# MCU1.net
KiCad netlist of a schematic drawn in Altium Designer
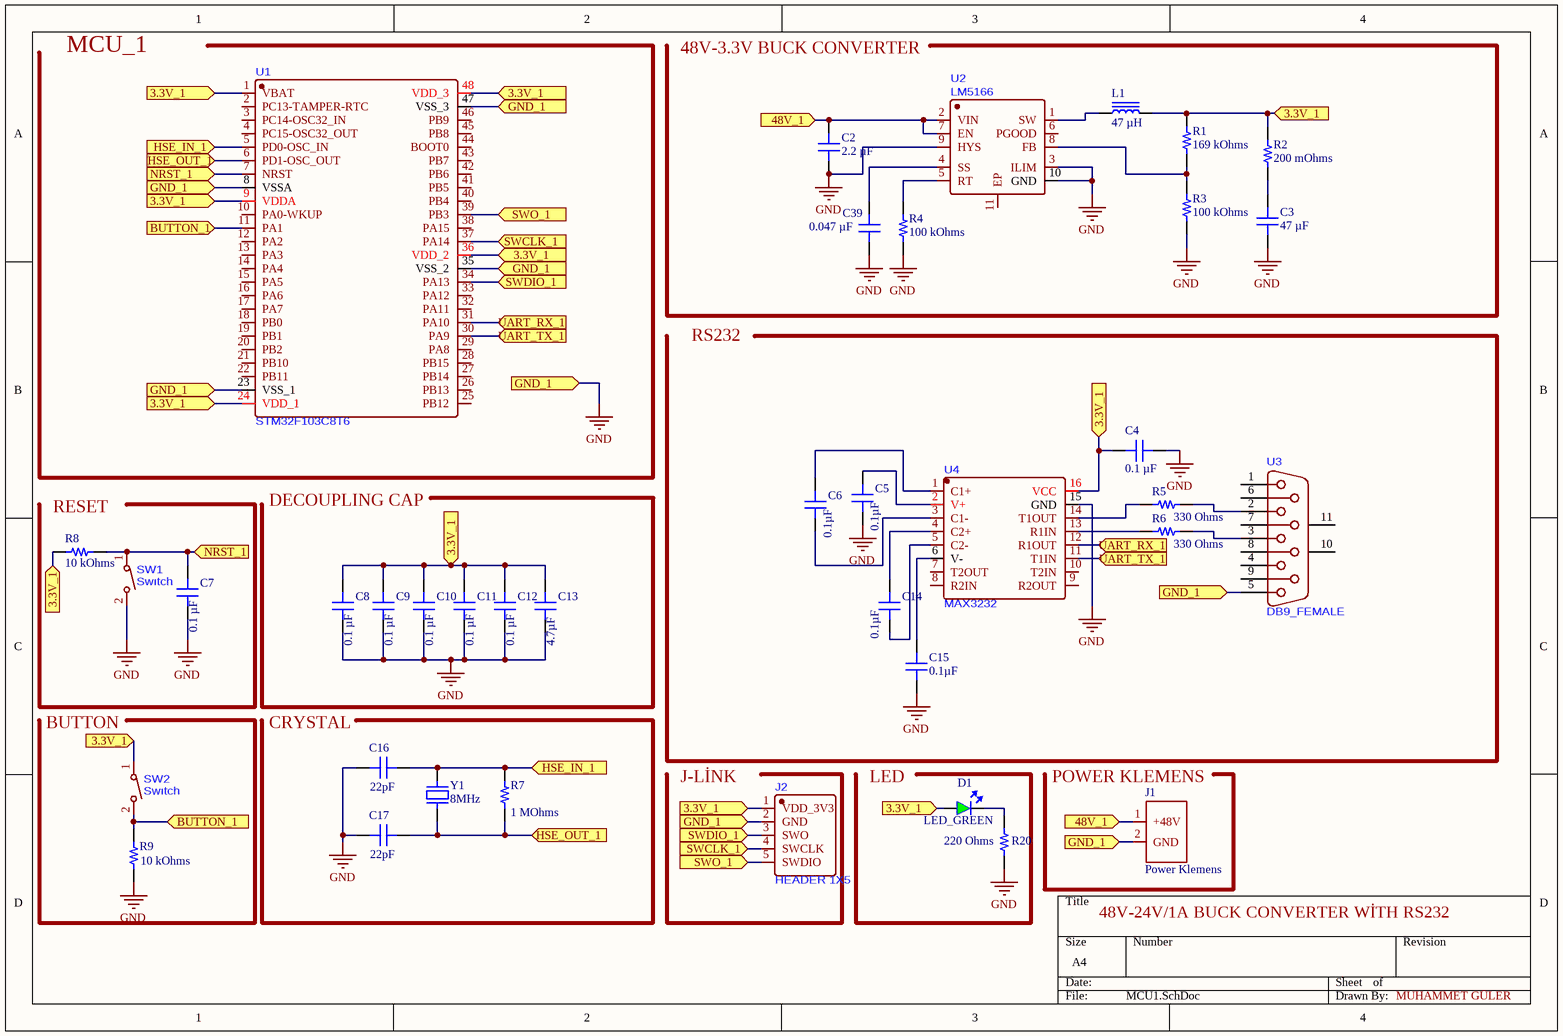
[diagram p0: MCU1.SchDoc]

(export (version "E")
  (design (tool "Eeschema 10.0.6"))
  (components
    (comp (ref "C2")
      (value "2.2 µF")
      (footprint "CAP 1210_3225 - 1MM")
      (description "CAP CER 2.2UF 100V X7R 1210")
      (fields
        (field (name "PART NUMBER") "1210BB225K101NGX085T")
        (field (name "MANUFACTURER") "Knowles Novacap")
      )
      (libsource (lib "Celestial Altium Library - altium_library") (part "Capacitor"))
    )
    (comp (ref "C3")
      (value "47 µF")
      (footprint "CAP 1210_3225 - 1MM")
      (description "CAP CER 47UF 10V X5R 1210")
      (fields (field (name "PART NUMBER") "885012109007") (field (name "MANUFACTURER") "Würth Elektronik"))
      (libsource (lib "Celestial Altium Library - altium_library") (part "Capacitor"))
    )
    (comp (ref "C4")
      (value "0.1 µF")
      (footprint "CAP 0603_1608")
      (description "CAP CER 0.1UF 6.3V X7R 0603")
      (fields
        (field (name "PART NUMBER") "6R3X14W104MV4T")
        (field (name "MANUFACTURER") "Johanson Dielectrics Inc.")
      )
      (libsource (lib "Celestial Altium Library - altium_library") (part "Capacitor"))
    )
    (comp (ref "C5")
      (value "0.1µF")
      (footprint "CAP 0603_1608")
      (description "CAP CER 0.1UF 16V X7R 0603")
      (fields (field (name "PART NUMBER") "0603YC104MAT2A") (field (name "MANUFACTURER") "AVX Corporation"))
      (libsource (lib "Celestial Altium Library - altium_library") (part "Capacitor"))
    )
    (comp (ref "C6")
      (value "0.1µF")
      (footprint "CAP 0603_1608")
      (description "CAP CER 0.1UF 16V X7R 0603")
      (fields (field (name "PART NUMBER") "0603YC104MAT2A") (field (name "MANUFACTURER") "AVX Corporation"))
      (libsource (lib "Celestial Altium Library - altium_library") (part "Capacitor"))
    )
    (comp (ref "C7")
      (value "0.1 µF")
      (footprint "CAP 0603_1608")
      (description "CAP CER 0.1UF 6.3V X7R 0603")
      (fields (field (name "PART NUMBER") "6R3X14W104MV4T"))
      (libsource (lib "Celestial Altium Library - altium_library") (part "Capacitor"))
    )
    (comp (ref "C8")
      (value "0.1 µF")
      (footprint "CAP 0603_1608")
      (description "CAP CER 0.1UF 6.3V X7R 0603")
      (fields (field (name "PART NUMBER") "6R3X14W104MV4T"))
      (libsource (lib "Celestial Altium Library - altium_library") (part "Capacitor"))
    )
    (comp (ref "C9")
      (value "0.1 µF")
      (footprint "CAP 0603_1608")
      (description "CAP CER 0.1UF 6.3V X7R 0603")
      (fields (field (name "PART NUMBER") "6R3X14W104MV4T"))
      (libsource (lib "Celestial Altium Library - altium_library") (part "Capacitor"))
    )
    (comp (ref "C10")
      (value "0.1 µF")
      (footprint "CAP 0603_1608")
      (description "CAP CER 0.1UF 6.3V X7R 0603")
      (fields (field (name "PART NUMBER") "6R3X14W104MV4T"))
      (libsource (lib "Celestial Altium Library - altium_library") (part "Capacitor"))
    )
    (comp (ref "C11")
      (value "0.1 µF")
      (footprint "CAP 0603_1608")
      (description "CAP CER 0.1UF 6.3V X7R 0603")
      (fields (field (name "PART NUMBER") "6R3X14W104MV4T"))
      (libsource (lib "Celestial Altium Library - altium_library") (part "Capacitor"))
    )
    (comp (ref "C12")
      (value "0.1 µF")
      (footprint "CAP 0603_1608")
      (description "CAP CER 0.1UF 6.3V X7R 0603")
      (fields (field (name "PART NUMBER") "6R3X14W104MV4T"))
      (libsource (lib "Celestial Altium Library - altium_library") (part "Capacitor"))
    )
    (comp (ref "C13")
      (value "4.7µF")
      (footprint "CAP 0603_1608")
      (description "CAP CER 4.7UF 6.3V X5R 0603")
      (fields (field (name "PART NUMBER") "06036D475KAT4A"))
      (libsource (lib "Celestial Altium Library - altium_library") (part "Capacitor"))
    )
    (comp (ref "C14")
      (value "0.1µF")
      (footprint "CAP 0603_1608")
      (description "CAP CER 0.1UF 16V X7R 0603")
      (fields (field (name "PART NUMBER") "0603YC104MAT2A") (field (name "MANUFACTURER") "AVX Corporation"))
      (libsource (lib "Celestial Altium Library - altium_library") (part "Capacitor"))
    )
    (comp (ref "C15")
      (value "0.1µF")
      (footprint "CAP 0603_1608")
      (description "CAP CER 0.1UF 16V X7R 0603")
      (fields (field (name "PART NUMBER") "0603YC104MAT2A") (field (name "MANUFACTURER") "AVX Corporation"))
      (libsource (lib "Celestial Altium Library - altium_library") (part "Capacitor"))
    )
    (comp (ref "C16")
      (value "22pF")
      (footprint "CAP 0603_1608")
      (description "CAP CER 22PF 6.3V NP0 0603")
      (fields (field (name "PART NUMBER") "06036A220J4T2A"))
      (libsource (lib "Celestial Altium Library - altium_library") (part "Capacitor"))
    )
    (comp (ref "C17")
      (value "22pF")
      (footprint "CAP 0603_1608")
      (description "CAP CER 22PF 6.3V NP0 0603")
      (fields (field (name "PART NUMBER") "06036A220J4T2A"))
      (libsource (lib "Celestial Altium Library - altium_library") (part "Capacitor"))
    )
    (comp (ref "C39")
      (value "0.047 µF")
      (footprint "CAP 0402_1005")
      (description "CAP CER 0402 47NF 16V X7R 10%")
      (fields (field (name "PART NUMBER") "C0402C473K3REC7867") (field (name "MANUFACTURER") "KEMET"))
      (libsource (lib "Celestial Altium Library - altium_library") (part "Capacitor"))
    )
    (comp (ref "D1")
      (value "LED_GREEN")
      (footprint "LED_GREEN")
      (libsource (lib "Schlib1") (part "LED_GREEN"))
    )
    (comp (ref "J1")
      (value "Power Klemens")
      (footprint "PCBComponent_1")
      (libsource (lib "Schlib1") (part "Power Klemens"))
    )
    (comp (ref "J2")
      (value "HEADER 1X5")
      (footprint "1X5-PIN-HEADER-2.54MM_ES")
      (libsource (lib "Schlib1") (part "HEADER 1X5 COPY"))
    )
    (comp (ref "L1")
      (value "47 µH")
      (footprint "TAIYO YUDEN NRS8030")
      (description "FIXED IND 47UH 1.3A 221 MOHM SMD")
      (fields (field (name "PART NUMBER") "NRS8030T470MJGJ") (field (name "MANUFACTURER") "Taiyo Yuden"))
      (libsource (lib "Celestial Altium Library - altium_library") (part "Inductor"))
    )
    (comp (ref "R1")
      (value "169 kOhms")
      (footprint "RES 0402_1005")
      (description "RES 169K OHM 1% 1/16W 0402")
      (fields (field (name "PART NUMBER") "RC0402FR-07169KL") (field (name "MANUFACTURER") "Yageo"))
      (libsource (lib "Celestial Altium Library - altium_library") (part "Resistor"))
    )
    (comp (ref "R2")
      (value "200 mOhms")
      (footprint "RES 0402_1005")
      (description "RES 0.2 OHM 1% 1/16W 0402")
      (fields
        (field (name "PART NUMBER") "MFL0402R2000FP")
        (field (name "MANUFACTURER") "Eaton - Electronics Division")
      )
      (libsource (lib "Celestial Altium Library - altium_library") (part "Resistor"))
    )
    (comp (ref "R3")
      (value "100 kOhms")
      (footprint "RES 0402_1005")
      (description "RES SMD 100K OHM 5% 1/16W 0402")
      (fields (field (name "PART NUMBER") "AC0402JR-07100KL") (field (name "MANUFACTURER") "Yageo"))
      (libsource (lib "Celestial Altium Library - altium_library") (part "Resistor"))
    )
    (comp (ref "R4")
      (value "100 kOhms")
      (footprint "RES 0402_1005")
      (description "RES SMD 100K OHM 5% 1/16W 0402")
      (fields (field (name "PART NUMBER") "AC0402JR-07100KL") (field (name "MANUFACTURER") "Yageo"))
      (libsource (lib "Celestial Altium Library - altium_library") (part "Resistor"))
    )
    (comp (ref "R5")
      (value "330 Ohms")
      (footprint "RES 0603_1608")
      (description "RES SMD 330 OHM 1% 1/5W 0603")
      (fields
        (field (name "PART NUMBER") "CRGH0603F330R")
        (field (name "MANUFACTURER") "TE Connectivity Passive Product")
      )
      (libsource (lib "Celestial Altium Library - altium_library") (part "Resistor"))
    )
    (comp (ref "R6")
      (value "330 Ohms")
      (footprint "RES 0603_1608")
      (description "RES SMD 330 OHM 1% 1/5W 0603")
      (fields
        (field (name "PART NUMBER") "CRGH0603F330R")
        (field (name "MANUFACTURER") "TE Connectivity Passive Product")
      )
      (libsource (lib "Celestial Altium Library - altium_library") (part "Resistor"))
    )
    (comp (ref "R7")
      (value "1 MOhms")
      (footprint "RES 0603_1608")
      (description "RES SMD 1M OHM 1% 1/10W 0603")
      (fields (field (name "PART NUMBER") "RT0603FRE071ML"))
      (libsource (lib "Celestial Altium Library - altium_library") (part "Resistor"))
    )
    (comp (ref "R8")
      (value "10 kOhms")
      (footprint "RES 0603_1608")
      (description "RES 10K OHM 0.1% 1/16W 0603")
      (fields
        (field (name "PART NUMBER") "RNCS0603BKE10K0")
        (field (name "MANUFACTURER") "Stackpole Electronics Inc")
      )
      (libsource (lib "Celestial Altium Library - altium_library") (part "Resistor"))
    )
    (comp (ref "R9")
      (value "10 kOhms")
      (footprint "RES 0603_1608")
      (description "RES SMD 10K OHM 0.1% 1/16W 0603")
      (fields (field (name "PART NUMBER") "CPF0603B10KE"))
      (libsource (lib "Celestial Altium Library - altium_library") (part "Resistor"))
    )
    (comp (ref "R20")
      (value "220 Ohms")
      (footprint "RES 0603_1608")
      (description "RES SMD 220 OHM 5% 1/3W 0603")
      (fields (field (name "PART NUMBER") "CRCW0603220RJNEAHP") (field (name "MANUFACTURER") "Vishay Dale"))
      (libsource (lib "Celestial Altium Library - altium_library") (part "Resistor"))
    )
    (comp (ref "SW1")
      (value "Swıtch")
      (footprint "SW-SMD_L4.0-W3.0-LS5.0")
      (libsource (lib "Schlib1") (part "Swıtch"))
    )
    (comp (ref "SW2")
      (value "Swıtch")
      (footprint "SW-SMD_L4.0-W3.0-LS5.0")
      (libsource (lib "Schlib1") (part "Swıtch"))
    )
    (comp (ref "U1")
      (value "STM32F103C8T6")
      (footprint "UFQFPN-48_STM32")
      (libsource (lib "Schlib1") (part "STM32F103C8T6"))
    )
    (comp (ref "U2")
      (value "LM5166")
      (footprint "VSON-10_L3.0-W3.0-P0.50-TL-EP-1")
      (libsource (lib "Schlib1") (part "LM5166DRCR"))
    )
    (comp (ref "U3")
      (value "DB9_FEMALE")
      (footprint "DB9-TH_DB9F_C5164093")
      (libsource (lib "Schlib1") (part "5745781-4"))
    )
    (comp (ref "U4")
      (value "MAX3232")
      (footprint "SOP-16_L9.9-W3.9-P1.27-LS6.0-BL")
      (libsource (lib "Schlib1") (part "MAX3232ESE-MS"))
    )
    (comp (ref "Y1")
      (value "8MHz")
      (footprint "NDK NX8045GB")
      (description "CRYSTAL 8.0000MHZ 8PF SMD")
      (fields
        (field (name "PART NUMBER") "NX8045GB-8.000M-STD-CSF-4")
        (field (name "MANUFACTURER") "NDK America, Inc.")
      )
      (libsource (lib "Celestial Altium Library - altium_library") (part "NDK Crystal NX8045GB"))
    )
  )
  (nets
    (net (code "1") (name "/3.3V_1") (class "Default")
      (node (ref "C10") (pin "2") (pinfunction "2_2") (pintype "passive"))
      (node (ref "C11") (pin "2") (pinfunction "2_2") (pintype "passive"))
      (node (ref "C12") (pin "2") (pinfunction "2_2") (pintype "passive"))
      (node (ref "C13") (pin "2") (pinfunction "2_2") (pintype "passive"))
      (node (ref "C4") (pin "2") (pinfunction "2_2") (pintype "passive"))
      (node (ref "C8") (pin "2") (pinfunction "2_2") (pintype "passive"))
      (node (ref "C9") (pin "2") (pinfunction "2_2") (pintype "passive"))
      (node (ref "D1") (pin "1") (pinfunction "IN_1") (pintype "passive"))
      (node (ref "J2") (pin "1") (pinfunction "VDD_3V3_1") (pintype "passive"))
      (node (ref "L1") (pin "2") (pinfunction "2_2") (pintype "passive"))
      (node (ref "R1") (pin "2") (pinfunction "2_2") (pintype "passive"))
      (node (ref "R2") (pin "2") (pinfunction "2_2") (pintype "passive"))
      (node (ref "R8") (pin "2") (pinfunction "2_2") (pintype "passive"))
      (node (ref "SW2") (pin "1") (pinfunction "1_1") (pintype "passive"))
      (node (ref "U1") (pin "1") (pinfunction "VBAT_1") (pintype "passive"))
      (node (ref "U1") (pin "24") (pinfunction "VDD_1_24") (pintype "passive"))
      (node (ref "U1") (pin "36") (pinfunction "VDD_2_36") (pintype "passive"))
      (node (ref "U1") (pin "48") (pinfunction "VDD_3_48") (pintype "passive"))
      (node (ref "U1") (pin "9") (pinfunction "VDDA_9") (pintype "passive"))
      (node (ref "U4") (pin "16") (pinfunction "VCC_16") (pintype "passive"))
    )
    (net (code "2") (name "/48V_1") (class "Default")
      (node (ref "C2") (pin "2") (pinfunction "2_2") (pintype "passive"))
      (node (ref "J1") (pin "1") (pinfunction "+48V_1") (pintype "passive"))
      (node (ref "U2") (pin "2") (pinfunction "VIN_2") (pintype "passive"))
      (node (ref "U2") (pin "7") (pinfunction "EN_7") (pintype "passive"))
    )
    (net (code "3") (name "/BUTTON_1") (class "Default")
      (node (ref "R9") (pin "2") (pinfunction "2_2") (pintype "passive"))
      (node (ref "SW2") (pin "2") (pinfunction "2_2") (pintype "passive"))
      (node (ref "U1") (pin "11") (pinfunction "PA1_11") (pintype "passive"))
    )
    (net (code "4") (name "/HSE_IN_1") (class "Default")
      (node (ref "C16") (pin "2") (pinfunction "2_2") (pintype "passive"))
      (node (ref "R7") (pin "2") (pinfunction "2_2") (pintype "passive"))
      (node (ref "U1") (pin "5") (pinfunction "PD0-OSC_IN_5") (pintype "passive"))
      (node (ref "Y1") (pin "2") (pinfunction "2_2") (pintype "passive"))
    )
    (net (code "5") (name "/HSE_OUT_1") (class "Default")
      (node (ref "C17") (pin "2") (pinfunction "2_2") (pintype "passive"))
      (node (ref "R7") (pin "1") (pinfunction "1_1") (pintype "passive"))
      (node (ref "U1") (pin "6") (pinfunction "PD1-OSC_OUT_6") (pintype "passive"))
      (node (ref "Y1") (pin "1") (pinfunction "1_1") (pintype "passive"))
    )
    (net (code "6") (name "/NRST_1") (class "Default")
      (node (ref "C7") (pin "2") (pinfunction "2_2") (pintype "passive"))
      (node (ref "R8") (pin "1") (pinfunction "1_1") (pintype "passive"))
      (node (ref "SW1") (pin "1") (pinfunction "1_1") (pintype "passive"))
      (node (ref "U1") (pin "7") (pinfunction "NRST_7") (pintype "passive"))
    )
    (net (code "7") (name "/SWCLK_1") (class "Default")
      (node (ref "J2") (pin "4") (pinfunction "SWCLK_4") (pintype "passive"))
      (node (ref "U1") (pin "37") (pinfunction "PA14_37") (pintype "passive"))
    )
    (net (code "8") (name "/SWDIO_1") (class "Default")
      (node (ref "J2") (pin "3") (pinfunction "SWO_3") (pintype "passive"))
      (node (ref "U1") (pin "34") (pinfunction "PA13_34") (pintype "passive"))
    )
    (net (code "9") (name "/SWO_1") (class "Default")
      (node (ref "J2") (pin "5") (pinfunction "SWDIO_5") (pintype "passive"))
      (node (ref "U1") (pin "39") (pinfunction "PB3_39") (pintype "passive"))
    )
    (net (code "10") (name "/UART_RX_1") (class "Default")
      (node (ref "U1") (pin "31") (pinfunction "PA10_31") (pintype "passive"))
      (node (ref "U4") (pin "12") (pinfunction "R1OUT_12") (pintype "passive"))
    )
    (net (code "11") (name "/UART_TX_1") (class "Default")
      (node (ref "U1") (pin "30") (pinfunction "PA9_30") (pintype "passive"))
      (node (ref "U4") (pin "11") (pinfunction "T1IN_11") (pintype "passive"))
    )
    (net (code "12") (name "GND") (class "Default")
      (node (ref "C10") (pin "1") (pinfunction "1_1") (pintype "passive"))
      (node (ref "C11") (pin "1") (pinfunction "1_1") (pintype "passive"))
      (node (ref "C12") (pin "1") (pinfunction "1_1") (pintype "passive"))
      (node (ref "C13") (pin "1") (pinfunction "1_1") (pintype "passive"))
      (node (ref "C15") (pin "1") (pinfunction "1_1") (pintype "passive"))
      (node (ref "C16") (pin "1") (pinfunction "1_1") (pintype "passive"))
      (node (ref "C17") (pin "1") (pinfunction "1_1") (pintype "passive"))
      (node (ref "C2") (pin "1") (pinfunction "1_1") (pintype "passive"))
      (node (ref "C3") (pin "1") (pinfunction "1_1") (pintype "passive"))
      (node (ref "C39") (pin "1") (pinfunction "1_1") (pintype "passive"))
      (node (ref "C4") (pin "1") (pinfunction "1_1") (pintype "passive"))
      (node (ref "C5") (pin "1") (pinfunction "1_1") (pintype "passive"))
      (node (ref "C7") (pin "1") (pinfunction "1_1") (pintype "passive"))
      (node (ref "C8") (pin "1") (pinfunction "1_1") (pintype "passive"))
      (node (ref "C9") (pin "1") (pinfunction "1_1") (pintype "passive"))
      (node (ref "J1") (pin "2") (pinfunction "GND_2") (pintype "passive"))
      (node (ref "J2") (pin "2") (pinfunction "GND_2") (pintype "passive"))
      (node (ref "R20") (pin "1") (pinfunction "1_1") (pintype "passive"))
      (node (ref "R3") (pin "1") (pinfunction "1_1") (pintype "passive"))
      (node (ref "R4") (pin "1") (pinfunction "1_1") (pintype "passive"))
      (node (ref "R9") (pin "1") (pinfunction "1_1") (pintype "passive"))
      (node (ref "SW1") (pin "2") (pinfunction "2_2") (pintype "passive"))
      (node (ref "U1") (pin "23") (pinfunction "VSS_1_23") (pintype "passive"))
      (node (ref "U1") (pin "35") (pinfunction "VSS_2_35") (pintype "passive"))
      (node (ref "U1") (pin "47") (pinfunction "VSS_3_47") (pintype "passive"))
      (node (ref "U1") (pin "8") (pinfunction "VSSA_8") (pintype "passive"))
      (node (ref "U2") (pin "10") (pinfunction "GND_10") (pintype "passive"))
      (node (ref "U2") (pin "3") (pinfunction "ILIM_3") (pintype "passive"))
      (node (ref "U2") (pin "9") (pinfunction "HYS_9") (pintype "passive"))
      (node (ref "U3") (pin "5") (pinfunction "5_5") (pintype "passive"))
      (node (ref "U4") (pin "15") (pinfunction "GND_15") (pintype "passive"))
    )
    (net (code "13") (name "Net-(C3-Pad2)") (class "Default")
      (node (ref "C3") (pin "2") (pinfunction "2_2") (pintype "passive"))
      (node (ref "R2") (pin "1") (pinfunction "1_1") (pintype "passive"))
    )
    (net (code "14") (name "Net-(D1-OUT)") (class "Default")
      (node (ref "D1") (pin "2") (pinfunction "OUT_2") (pintype "passive"))
      (node (ref "R20") (pin "2") (pinfunction "2_2") (pintype "passive"))
    )
    (net (code "15") (name "Net-(R5-Pad2)") (class "Default")
      (node (ref "R5") (pin "2") (pinfunction "2_2") (pintype "passive"))
      (node (ref "U3") (pin "2") (pinfunction "2_2") (pintype "passive"))
    )
    (net (code "16") (name "Net-(R6-Pad2)") (class "Default")
      (node (ref "R6") (pin "2") (pinfunction "2_2") (pintype "passive"))
      (node (ref "U3") (pin "3") (pinfunction "3_3") (pintype "passive"))
    )
    (net (code "17") (name "Net-(U2-FB)") (class "Default")
      (node (ref "R1") (pin "1") (pinfunction "1_1") (pintype "passive"))
      (node (ref "R3") (pin "2") (pinfunction "2_2") (pintype "passive"))
      (node (ref "U2") (pin "8") (pinfunction "FB_8") (pintype "passive"))
    )
    (net (code "18") (name "Net-(U2-RT)") (class "Default")
      (node (ref "R4") (pin "2") (pinfunction "2_2") (pintype "passive"))
      (node (ref "U2") (pin "5") (pinfunction "RT_5") (pintype "passive"))
    )
    (net (code "19") (name "Net-(U2-SS)") (class "Default")
      (node (ref "C39") (pin "2") (pinfunction "2_2") (pintype "passive"))
      (node (ref "U2") (pin "4") (pinfunction "SS_4") (pintype "passive"))
    )
    (net (code "20") (name "Net-(U2-SW)") (class "Default")
      (node (ref "L1") (pin "1") (pinfunction "1_1") (pintype "passive"))
      (node (ref "U2") (pin "1") (pinfunction "SW_1") (pintype "passive"))
    )
    (net (code "21") (name "Net-(U4-C1+)") (class "Default")
      (node (ref "C6") (pin "2") (pinfunction "2_2") (pintype "passive"))
      (node (ref "U4") (pin "1") (pinfunction "C1+_1") (pintype "passive"))
    )
    (net (code "22") (name "Net-(U4-C1-)") (class "Default")
      (node (ref "C6") (pin "1") (pinfunction "1_1") (pintype "passive"))
      (node (ref "U4") (pin "3") (pinfunction "C1-_3") (pintype "passive"))
    )
    (net (code "23") (name "Net-(U4-C2+)") (class "Default")
      (node (ref "C14") (pin "2") (pinfunction "2_2") (pintype "passive"))
      (node (ref "U4") (pin "4") (pinfunction "C2+_4") (pintype "passive"))
    )
    (net (code "24") (name "Net-(U4-C2-)") (class "Default")
      (node (ref "C14") (pin "1") (pinfunction "1_1") (pintype "passive"))
      (node (ref "U4") (pin "5") (pinfunction "C2-_5") (pintype "passive"))
    )
    (net (code "25") (name "Net-(U4-R1IN)") (class "Default")
      (node (ref "R6") (pin "1") (pinfunction "1_1") (pintype "passive"))
      (node (ref "U4") (pin "13") (pinfunction "R1IN_13") (pintype "passive"))
    )
    (net (code "26") (name "Net-(U4-T1OUT)") (class "Default")
      (node (ref "R5") (pin "1") (pinfunction "1_1") (pintype "passive"))
      (node (ref "U4") (pin "14") (pinfunction "T1OUT_14") (pintype "passive"))
    )
    (net (code "27") (name "Net-(U4-V+)") (class "Default")
      (node (ref "C5") (pin "2") (pinfunction "2_2") (pintype "passive"))
      (node (ref "U4") (pin "2") (pinfunction "V+_2") (pintype "passive"))
    )
    (net (code "28") (name "Net-(U4-V-)") (class "Default")
      (node (ref "C15") (pin "2") (pinfunction "2_2") (pintype "passive"))
      (node (ref "U4") (pin "6") (pinfunction "V-_6") (pintype "passive"))
    )
    (net (code "29") (name "unconnected-(U1-BOOT0-Pad44)") (class "Default")
      (node (ref "U1") (pin "44") (pinfunction "BOOT0_44") (pintype "passive"))
    )
    (net (code "30") (name "unconnected-(U1-PA0-WKUP-Pad10)") (class "Default")
      (node (ref "U1") (pin "10") (pinfunction "PA0-WKUP_10") (pintype "passive"))
    )
    (net (code "31") (name "unconnected-(U1-PA2-Pad12)") (class "Default")
      (node (ref "U1") (pin "12") (pinfunction "PA2_12") (pintype "passive"))
    )
    (net (code "32") (name "unconnected-(U1-PA3-Pad13)") (class "Default")
      (node (ref "U1") (pin "13") (pinfunction "PA3_13") (pintype "passive"))
    )
    (net (code "33") (name "unconnected-(U1-PA4-Pad14)") (class "Default")
      (node (ref "U1") (pin "14") (pinfunction "PA4_14") (pintype "passive"))
    )
    (net (code "34") (name "unconnected-(U1-PA5-Pad15)") (class "Default")
      (node (ref "U1") (pin "15") (pinfunction "PA5_15") (pintype "passive"))
    )
    (net (code "35") (name "unconnected-(U1-PA6-Pad16)") (class "Default")
      (node (ref "U1") (pin "16") (pinfunction "PA6_16") (pintype "passive"))
    )
    (net (code "36") (name "unconnected-(U1-PA7-Pad17)") (class "Default")
      (node (ref "U1") (pin "17") (pinfunction "PA7_17") (pintype "passive"))
    )
    (net (code "37") (name "unconnected-(U1-PA8-Pad29)") (class "Default")
      (node (ref "U1") (pin "29") (pinfunction "PA8_29") (pintype "passive"))
    )
    (net (code "38") (name "unconnected-(U1-PA11-Pad32)") (class "Default")
      (node (ref "U1") (pin "32") (pinfunction "PA11_32") (pintype "passive"))
    )
    (net (code "39") (name "unconnected-(U1-PA12-Pad33)") (class "Default")
      (node (ref "U1") (pin "33") (pinfunction "PA12_33") (pintype "passive"))
    )
    (net (code "40") (name "unconnected-(U1-PA15-Pad38)") (class "Default")
      (node (ref "U1") (pin "38") (pinfunction "PA15_38") (pintype "passive"))
    )
    (net (code "41") (name "unconnected-(U1-PB0-Pad18)") (class "Default")
      (node (ref "U1") (pin "18") (pinfunction "PB0_18") (pintype "passive"))
    )
    (net (code "42") (name "unconnected-(U1-PB1-Pad19)") (class "Default")
      (node (ref "U1") (pin "19") (pinfunction "PB1_19") (pintype "passive"))
    )
    (net (code "43") (name "unconnected-(U1-PB2-Pad20)") (class "Default")
      (node (ref "U1") (pin "20") (pinfunction "PB2_20") (pintype "passive"))
    )
    (net (code "44") (name "unconnected-(U1-PB4-Pad40)") (class "Default")
      (node (ref "U1") (pin "40") (pinfunction "PB4_40") (pintype "passive"))
    )
    (net (code "45") (name "unconnected-(U1-PB5-Pad41)") (class "Default")
      (node (ref "U1") (pin "41") (pinfunction "PB5_41") (pintype "passive"))
    )
    (net (code "46") (name "unconnected-(U1-PB6-Pad42)") (class "Default")
      (node (ref "U1") (pin "42") (pinfunction "PB6_42") (pintype "passive"))
    )
    (net (code "47") (name "unconnected-(U1-PB7-Pad43)") (class "Default")
      (node (ref "U1") (pin "43") (pinfunction "PB7_43") (pintype "passive"))
    )
    (net (code "48") (name "unconnected-(U1-PB8-Pad45)") (class "Default")
      (node (ref "U1") (pin "45") (pinfunction "PB8_45") (pintype "passive"))
    )
    (net (code "49") (name "unconnected-(U1-PB9-Pad46)") (class "Default")
      (node (ref "U1") (pin "46") (pinfunction "PB9_46") (pintype "passive"))
    )
    (net (code "50") (name "unconnected-(U1-PB10-Pad21)") (class "Default")
      (node (ref "U1") (pin "21") (pinfunction "PB10_21") (pintype "passive"))
    )
    (net (code "51") (name "unconnected-(U1-PB11-Pad22)") (class "Default")
      (node (ref "U1") (pin "22") (pinfunction "PB11_22") (pintype "passive"))
    )
    (net (code "52") (name "unconnected-(U1-PB12-Pad25)") (class "Default")
      (node (ref "U1") (pin "25") (pinfunction "PB12_25") (pintype "passive"))
    )
    (net (code "53") (name "unconnected-(U1-PB13-Pad26)") (class "Default")
      (node (ref "U1") (pin "26") (pinfunction "PB13_26") (pintype "passive"))
    )
    (net (code "54") (name "unconnected-(U1-PB14-Pad27)") (class "Default")
      (node (ref "U1") (pin "27") (pinfunction "PB14_27") (pintype "passive"))
    )
    (net (code "55") (name "unconnected-(U1-PB15-Pad28)") (class "Default")
      (node (ref "U1") (pin "28") (pinfunction "PB15_28") (pintype "passive"))
    )
    (net (code "56") (name "unconnected-(U1-PC13-TAMPER-RTC-Pad2)") (class "Default")
      (node (ref "U1") (pin "2") (pinfunction "PC13-TAMPER-RTC_2") (pintype "passive"))
    )
    (net (code "57") (name "unconnected-(U1-PC14-OSC32_IN-Pad3)") (class "Default")
      (node (ref "U1") (pin "3") (pinfunction "PC14-OSC32_IN_3") (pintype "passive"))
    )
    (net (code "58") (name "unconnected-(U1-PC15-OSC32_OUT-Pad4)") (class "Default")
      (node (ref "U1") (pin "4") (pinfunction "PC15-OSC32_OUT_4") (pintype "passive"))
    )
    (net (code "59") (name "unconnected-(U2-EP-Pad11)") (class "Default")
      (node (ref "U2") (pin "11") (pinfunction "EP_11") (pintype "passive"))
    )
    (net (code "60") (name "unconnected-(U2-PGOOD-Pad6)") (class "Default")
      (node (ref "U2") (pin "6") (pinfunction "PGOOD_6") (pintype "passive"))
    )
    (net (code "61") (name "unconnected-(U3-MH1-Pad10)") (class "Default")
      (node (ref "U3") (pin "10") (pinfunction "MH1_10") (pintype "passive"))
    )
    (net (code "62") (name "unconnected-(U3-MH2-Pad11)") (class "Default")
      (node (ref "U3") (pin "11") (pinfunction "MH2_11") (pintype "passive"))
    )
    (net (code "63") (name "unconnected-(U3-Pad1)") (class "Default")
      (node (ref "U3") (pin "1") (pinfunction "1_1") (pintype "passive"))
    )
    (net (code "64") (name "unconnected-(U3-Pad4)") (class "Default")
      (node (ref "U3") (pin "4") (pinfunction "4_4") (pintype "passive"))
    )
    (net (code "65") (name "unconnected-(U3-Pad6)") (class "Default")
      (node (ref "U3") (pin "6") (pinfunction "6_6") (pintype "passive"))
    )
    (net (code "66") (name "unconnected-(U3-Pad7)") (class "Default")
      (node (ref "U3") (pin "7") (pinfunction "7_7") (pintype "passive"))
    )
    (net (code "67") (name "unconnected-(U3-Pad8)") (class "Default")
      (node (ref "U3") (pin "8") (pinfunction "8_8") (pintype "passive"))
    )
    (net (code "68") (name "unconnected-(U3-Pad9)") (class "Default")
      (node (ref "U3") (pin "9") (pinfunction "9_9") (pintype "passive"))
    )
    (net (code "69") (name "unconnected-(U4-R2IN-Pad8)") (class "Default")
      (node (ref "U4") (pin "8") (pinfunction "R2IN_8") (pintype "passive"))
    )
    (net (code "70") (name "unconnected-(U4-R2OUT-Pad9)") (class "Default")
      (node (ref "U4") (pin "9") (pinfunction "R2OUT_9") (pintype "passive"))
    )
    (net (code "71") (name "unconnected-(U4-T2IN-Pad10)") (class "Default")
      (node (ref "U4") (pin "10") (pinfunction "T2IN_10") (pintype "passive"))
    )
    (net (code "72") (name "unconnected-(U4-T2OUT-Pad7)") (class "Default")
      (node (ref "U4") (pin "7") (pinfunction "T2OUT_7") (pintype "passive"))
    )
  )
)
